# main_shema.net
KiCad netlist of a schematic drawn in EAGLE
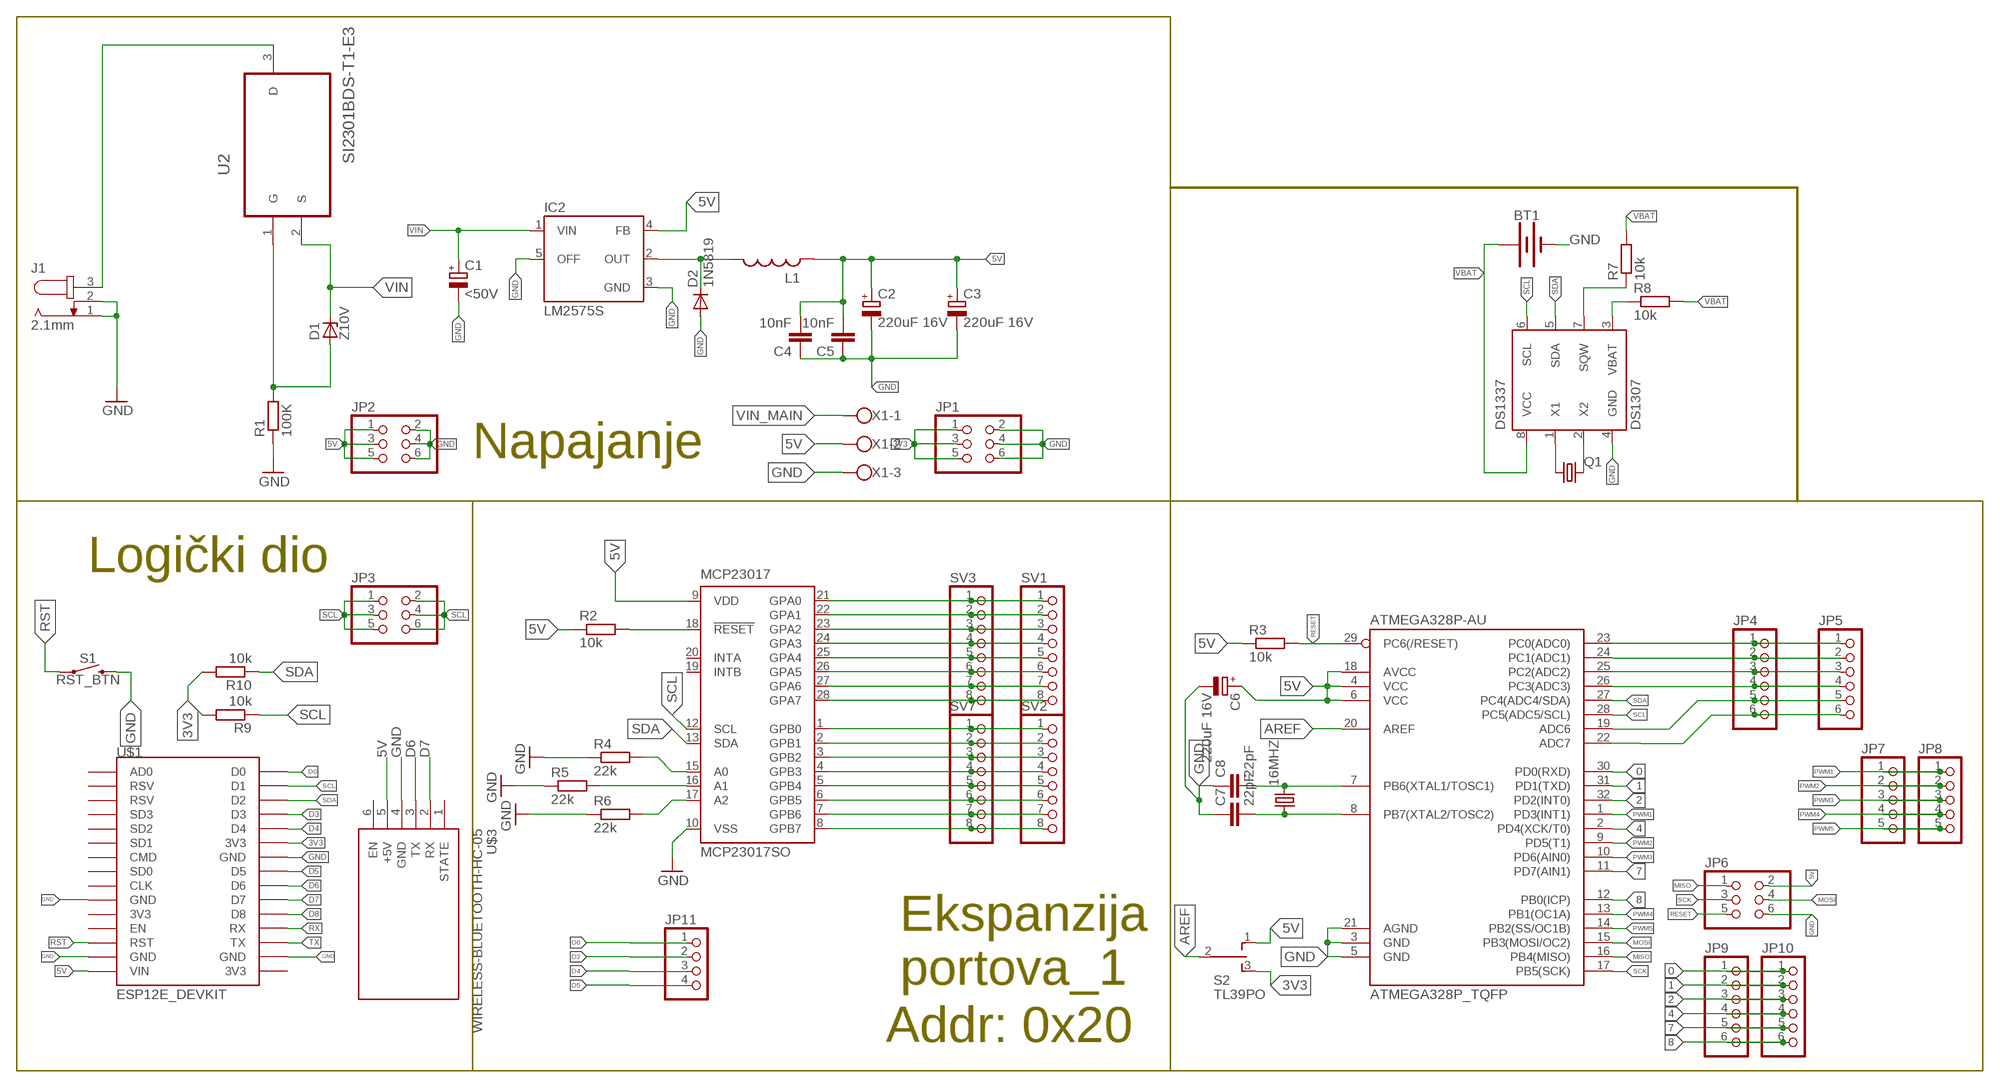
[diagram p0: schematic, sheet 1]

(export (version "E")
  (design (tool "Eeschema 10.0.6"))
  (components
    (comp (ref "16MHZ")
      (value "CRYSTALHC49S")
      (footprint "eagle-import:HC49_S")
      (libsource (lib "eagle-import") (part "crystal_204_CRYSTALHC49S"))
    )
    (comp (ref "ATMEGA328P-AU")
      (value "ATMEGA328P_TQFP")
      (footprint "eagle-import:TQFP32-08")
      (libsource (lib "eagle-import") (part "ATMEGA328P_TQFP"))
    )
    (comp (ref "BT1")
      (value "BATTERY-20MM_PTH")
      (footprint "eagle-import:BATTCOM_20MM_PTH")
      (libsource (lib "eagle-import") (part "BATTERY-20MM_PTH"))
    )
    (comp (ref "C1")
      (value "<50V")
      (footprint "eagle-import:E3,5-8")
      (libsource (lib "eagle-import") (part "CPOL-EUE3.5-8"))
    )
    (comp (ref "C2")
      (value "220uF 16V")
      (footprint "eagle-import:E2-5")
      (libsource (lib "eagle-import") (part "CPOL-EUE2-5"))
    )
    (comp (ref "C3")
      (value "220uF 16V")
      (footprint "eagle-import:E2-5")
      (libsource (lib "eagle-import") (part "CPOL-EUE2-5"))
    )
    (comp (ref "C4")
      (value "10nF")
      (footprint "eagle-import:C025-024X044")
      (libsource (lib "eagle-import") (part "C-EU025-024X044"))
    )
    (comp (ref "C5")
      (value "10nF")
      (footprint "eagle-import:C025-024X044")
      (libsource (lib "eagle-import") (part "C-EU025-024X044"))
    )
    (comp (ref "C6")
      (value "220uF 16V")
      (footprint "eagle-import:E2-5")
      (libsource (lib "eagle-import") (part "CPOL-EUE2-5"))
    )
    (comp (ref "C7")
      (value "22pF")
      (footprint "eagle-import:C025-024X044")
      (libsource (lib "eagle-import") (part "C-EU025-024X044"))
    )
    (comp (ref "C8")
      (value "22pF")
      (footprint "eagle-import:C025-024X044")
      (libsource (lib "eagle-import") (part "C-EU025-024X044"))
    )
    (comp (ref "D1")
      (value "Z10V")
      (footprint "eagle-import:DO35Z10")
      (libsource (lib "eagle-import") (part "ZENER-DIODEDO35Z10"))
    )
    (comp (ref "D2")
      (value "1N5819")
      (footprint "eagle-import:DO41-10")
      (libsource (lib "eagle-import") (part "1N4004"))
    )
    (comp (ref "DS1337")
      (value "DS1307")
      (footprint "eagle-import:DIL08")
      (libsource (lib "eagle-import") (part "DS1307"))
    )
    (comp (ref "IC2")
      (value "LM2575S")
      (footprint "eagle-import:TO263-5")
      (libsource (lib "eagle-import") (part "LM2575S"))
    )
    (comp (ref "J1")
      (value "2.1mm")
      (footprint "eagle-import:SPC4078")
      (libsource (lib "eagle-import") (part "JACK-PLUG1"))
    )
    (comp (ref "JP1")
      (value "PINHD-2X3")
      (footprint "eagle-import:2X03")
      (libsource (lib "eagle-import") (part "pinhead_2_PINHD-2X3"))
    )
    (comp (ref "JP2")
      (value "PINHD-2X3")
      (footprint "eagle-import:2X03")
      (libsource (lib "eagle-import") (part "PINHD-2X3"))
    )
    (comp (ref "JP3")
      (value "PINHD-2X3")
      (footprint "eagle-import:2X03")
      (libsource (lib "eagle-import") (part "pinhead_2_PINHD-2X3"))
    )
    (comp (ref "JP4")
      (value "PINHD-1X6")
      (footprint "eagle-import:1X06")
      (libsource (lib "eagle-import") (part "PINHD-1X6"))
    )
    (comp (ref "JP5")
      (value "PINHD-1X6")
      (footprint "eagle-import:1X06")
      (libsource (lib "eagle-import") (part "PINHD-1X6"))
    )
    (comp (ref "JP6")
      (value "PINHD-2X3")
      (footprint "eagle-import:2X03")
      (libsource (lib "eagle-import") (part "pinhead_2_PINHD-2X3"))
    )
    (comp (ref "JP7")
      (value "PINHD-1X5")
      (footprint "eagle-import:1X05")
      (libsource (lib "eagle-import") (part "PINHD-1X5"))
    )
    (comp (ref "JP8")
      (value "PINHD-1X5")
      (footprint "eagle-import:1X05")
      (libsource (lib "eagle-import") (part "PINHD-1X5"))
    )
    (comp (ref "JP9")
      (value "PINHD-1X6")
      (footprint "eagle-import:1X06")
      (libsource (lib "eagle-import") (part "PINHD-1X6"))
    )
    (comp (ref "JP10")
      (value "PINHD-1X6")
      (footprint "eagle-import:1X06")
      (libsource (lib "eagle-import") (part "PINHD-1X6"))
    )
    (comp (ref "JP11")
      (value "PINHD-1X4")
      (footprint "eagle-import:1X04")
      (libsource (lib "eagle-import") (part "PINHD-1X4"))
    )
    (comp (ref "L1")
      (value "MSS1260")
      (footprint "eagle-import:MSS1260")
      (libsource (lib "eagle-import") (part "MSS1260"))
    )
    (comp (ref "MCP23017")
      (value "MCP23017SO")
      (footprint "eagle-import:SO28W")
      (fields (field (name "MF") "MICROCHIP") (field (name "MPN") "MCP23017-E/SO"))
      (libsource (lib "eagle-import") (part "MCP23017SO"))
    )
    (comp (ref "Q1")
      (value "CRYSTALTC38H")
      (footprint "eagle-import:TC38H")
      (libsource (lib "eagle-import") (part "CRYSTALTC38H"))
    )
    (comp (ref "R1")
      (value "100K")
      (footprint "eagle-import:R1206")
      (libsource (lib "eagle-import") (part "R-EU_R1206"))
    )
    (comp (ref "R2")
      (value "10k")
      (footprint "eagle-import:R1206")
      (libsource (lib "eagle-import") (part "R-EU_R1206"))
    )
    (comp (ref "R3")
      (value "10k")
      (footprint "eagle-import:R1206")
      (libsource (lib "eagle-import") (part "R-EU_R1206"))
    )
    (comp (ref "R4")
      (value "22k")
      (footprint "eagle-import:R1206")
      (libsource (lib "eagle-import") (part "R-EU_R1206"))
    )
    (comp (ref "R5")
      (value "22k")
      (footprint "eagle-import:R1206")
      (libsource (lib "eagle-import") (part "R-EU_R1206"))
    )
    (comp (ref "R6")
      (value "22k")
      (footprint "eagle-import:R1206")
      (libsource (lib "eagle-import") (part "R-EU_R1206"))
    )
    (comp (ref "R7")
      (value "10k")
      (footprint "eagle-import:R1206")
      (libsource (lib "eagle-import") (part "R-EU_R1206"))
    )
    (comp (ref "R8")
      (value "10k")
      (footprint "eagle-import:R1206")
      (libsource (lib "eagle-import") (part "R-EU_R1206"))
    )
    (comp (ref "R9")
      (value "10k")
      (footprint "eagle-import:R1206")
      (libsource (lib "eagle-import") (part "R-EU_R1206"))
    )
    (comp (ref "R10")
      (value "10k")
      (footprint "eagle-import:R1206")
      (libsource (lib "eagle-import") (part "R-EU_R1206"))
    )
    (comp (ref "S1")
      (value "RST_BTN")
      (footprint "eagle-import:TACTILE_SWITCH_PTH_6.0MM")
      (libsource (lib "eagle-import") (part "MOMENTARY-SWITCH-SPST-PTH-6.0MM"))
    )
    (comp (ref "S2")
      (value "TL39PO")
      (footprint "eagle-import:TL3XPO")
      (libsource (lib "eagle-import") (part "TL39PO"))
    )
    (comp (ref "SV1")
      (value "PINHD-1X8")
      (footprint "eagle-import:1X08")
      (libsource (lib "eagle-import") (part "PINHD-1X8"))
    )
    (comp (ref "SV2")
      (value "PINHD-1X8")
      (footprint "eagle-import:1X08")
      (libsource (lib "eagle-import") (part "PINHD-1X8"))
    )
    (comp (ref "SV3")
      (value "PINHD-1X8")
      (footprint "eagle-import:1X08")
      (libsource (lib "eagle-import") (part "PINHD-1X8"))
    )
    (comp (ref "SV7")
      (value "PINHD-1X8")
      (footprint "eagle-import:1X08")
      (libsource (lib "eagle-import") (part "PINHD-1X8"))
    )
    (comp (ref "U$1")
      (value "ESP12E_DEVKIT")
      (footprint "eagle-import:ESP12E_DEVKIT")
      (libsource (lib "eagle-import") (part "ESP12E_DEVKIT"))
    )
    (comp (ref "U$3")
      (value "WIRELESS-BLUETOOTH-HC-05")
      (footprint "eagle-import:WIRELESS-BLUETOOTH-HC-05")
      (libsource (lib "eagle-import") (part "WIRELESS-BLUETOOTH-HC-05"))
    )
    (comp (ref "U2")
      (value "SI2301BDS-T1-E3")
      (footprint "eagle-import:SOT95P237X112-3N")
      (libsource (lib "eagle-import") (part "SI2301BDS-T1-E3"))
    )
    (comp (ref "X1")
      (value "W237-103")
      (footprint "eagle-import:W237-103")
      (fields (field (name "MPN") "237-103"))
      (libsource (lib "eagle-import") (part "W237-103"))
    )
  )
  (nets
    (net (code "1") (name "0") (class "Default")
      (node (ref "ATMEGA328P-AU") (pin "30") (pinfunction "PD0(RXD)_30") (pintype "bidirectional"))
      (node (ref "JP10") (pin "1") (pinfunction "1_1") (pintype "passive"))
      (node (ref "JP9") (pin "1") (pinfunction "1_1") (pintype "passive"))
    )
    (net (code "2") (name "1") (class "Default")
      (node (ref "ATMEGA328P-AU") (pin "31") (pinfunction "PD1(TXD)_31") (pintype "bidirectional"))
      (node (ref "JP10") (pin "2") (pinfunction "2_2") (pintype "passive"))
      (node (ref "JP9") (pin "2") (pinfunction "2_2") (pintype "passive"))
    )
    (net (code "3") (name "2") (class "Default")
      (node (ref "ATMEGA328P-AU") (pin "32") (pinfunction "PD2(INT0)_32") (pintype "bidirectional"))
      (node (ref "JP10") (pin "3") (pinfunction "3_3") (pintype "passive"))
      (node (ref "JP9") (pin "3") (pinfunction "3_3") (pintype "passive"))
    )
    (net (code "4") (name "3V3") (class "Default")
      (node (ref "JP1") (pin "1") (pinfunction "1_1") (pintype "passive"))
      (node (ref "JP1") (pin "3") (pinfunction "3_3") (pintype "passive"))
      (node (ref "JP1") (pin "5") (pinfunction "5_5") (pintype "passive"))
      (node (ref "R10") (pin "2") (pinfunction "2_2") (pintype "passive"))
      (node (ref "R9") (pin "2") (pinfunction "2_2") (pintype "passive"))
      (node (ref "S2") (pin "3") (pinfunction "S_3") (pintype "passive"))
      (node (ref "U$1") (pin "3V3@1") (pinfunction "3V3_3V3@1") (pintype "bidirectional"))
    )
    (net (code "5") (name "4") (class "Default")
      (node (ref "ATMEGA328P-AU") (pin "2") (pinfunction "PD4(XCK/T0)_2") (pintype "bidirectional"))
      (node (ref "JP10") (pin "4") (pinfunction "4_4") (pintype "passive"))
      (node (ref "JP9") (pin "4") (pinfunction "4_4") (pintype "passive"))
    )
    (net (code "6") (name "5V") (class "Default")
      (node (ref "ATMEGA328P-AU") (pin "18") (pinfunction "AVCC_18") (pintype "bidirectional"))
      (node (ref "ATMEGA328P-AU") (pin "4") (pinfunction "VCC_4") (pintype "bidirectional"))
      (node (ref "ATMEGA328P-AU") (pin "6") (pinfunction "VCC_6") (pintype "bidirectional"))
      (node (ref "C2") (pin "+") (pinfunction "+_+") (pintype "passive"))
      (node (ref "C3") (pin "+") (pinfunction "+_+") (pintype "passive"))
      (node (ref "C4") (pin "2") (pinfunction "2_2") (pintype "passive"))
      (node (ref "C5") (pin "2") (pinfunction "2_2") (pintype "passive"))
      (node (ref "C6") (pin "+") (pinfunction "+_+") (pintype "passive"))
      (node (ref "IC2") (pin "4") (pinfunction "FB_4") (pintype "input"))
      (node (ref "JP2") (pin "1") (pinfunction "1_1") (pintype "passive"))
      (node (ref "JP2") (pin "3") (pinfunction "3_3") (pintype "passive"))
      (node (ref "JP2") (pin "5") (pinfunction "5_5") (pintype "passive"))
      (node (ref "JP6") (pin "2") (pinfunction "2_2") (pintype "passive"))
      (node (ref "L1") (pin "P$2") (pinfunction "P$2_P$2") (pintype "passive"))
      (node (ref "MCP23017") (pin "9") (pinfunction "VDD_9") (pintype "power_in"))
      (node (ref "R2") (pin "1") (pinfunction "1_1") (pintype "passive"))
      (node (ref "R3") (pin "1") (pinfunction "1_1") (pintype "passive"))
      (node (ref "S2") (pin "1") (pinfunction "O_1") (pintype "passive"))
      (node (ref "U$1") (pin "VIN") (pinfunction "VIN_VIN") (pintype "bidirectional"))
      (node (ref "U$3") (pin "5") (pinfunction "+5V_5") (pintype "power_in"))
      (node (ref "X1") (pin "2") (pinfunction "KL_2") (pintype "passive"))
    )
    (net (code "7") (name "7") (class "Default")
      (node (ref "ATMEGA328P-AU") (pin "11") (pinfunction "PD7(AIN1)_11") (pintype "bidirectional"))
      (node (ref "JP10") (pin "5") (pinfunction "5_5") (pintype "passive"))
      (node (ref "JP9") (pin "5") (pinfunction "5_5") (pintype "passive"))
    )
    (net (code "8") (name "8") (class "Default")
      (node (ref "ATMEGA328P-AU") (pin "12") (pinfunction "PB0(ICP)_12") (pintype "bidirectional"))
      (node (ref "JP10") (pin "6") (pinfunction "6_6") (pintype "passive"))
      (node (ref "JP9") (pin "6") (pinfunction "6_6") (pintype "passive"))
    )
    (net (code "9") (name "AREF") (class "Default")
      (node (ref "ATMEGA328P-AU") (pin "20") (pinfunction "AREF_20") (pintype "bidirectional"))
      (node (ref "S2") (pin "2") (pinfunction "P_2") (pintype "passive"))
    )
    (net (code "10") (name "D0") (class "Default")
      (node (ref "JP11") (pin "1") (pinfunction "1_1") (pintype "passive"))
      (node (ref "U$1") (pin "D0") (pinfunction "D0_D0") (pintype "bidirectional"))
    )
    (net (code "11") (name "D3") (class "Default")
      (node (ref "JP11") (pin "2") (pinfunction "2_2") (pintype "passive"))
      (node (ref "U$1") (pin "D3") (pinfunction "D3_D3") (pintype "bidirectional"))
    )
    (net (code "12") (name "D4") (class "Default")
      (node (ref "JP11") (pin "3") (pinfunction "3_3") (pintype "passive"))
      (node (ref "U$1") (pin "D4") (pinfunction "D4_D4") (pintype "bidirectional"))
    )
    (net (code "13") (name "D5") (class "Default")
      (node (ref "JP11") (pin "4") (pinfunction "4_4") (pintype "passive"))
      (node (ref "U$1") (pin "D5") (pinfunction "D5_D5") (pintype "bidirectional"))
    )
    (net (code "14") (name "D6") (class "Default")
      (node (ref "U$1") (pin "D6") (pinfunction "D6_D6") (pintype "bidirectional"))
      (node (ref "U$3") (pin "3") (pinfunction "TX_3") (pintype "bidirectional"))
    )
    (net (code "15") (name "D7") (class "Default")
      (node (ref "U$1") (pin "D7") (pinfunction "D7_D7") (pintype "bidirectional"))
      (node (ref "U$3") (pin "2") (pinfunction "RX_2") (pintype "bidirectional"))
    )
    (net (code "16") (name "D8") (class "Default")
      (node (ref "U$1") (pin "D8") (pinfunction "D8_D8") (pintype "bidirectional"))
    )
    (net (code "17") (name "GND") (class "Default")
      (node (ref "ATMEGA328P-AU") (pin "21") (pinfunction "AGND_21") (pintype "bidirectional"))
      (node (ref "ATMEGA328P-AU") (pin "3") (pinfunction "GND_3") (pintype "bidirectional"))
      (node (ref "ATMEGA328P-AU") (pin "5") (pinfunction "GND_5") (pintype "bidirectional"))
      (node (ref "BT1") (pin "2") (pinfunction "-_2") (pintype "power_in"))
      (node (ref "C1") (pin "-") (pinfunction "-_-") (pintype "passive"))
      (node (ref "C2") (pin "-") (pinfunction "-_-") (pintype "passive"))
      (node (ref "C3") (pin "-") (pinfunction "-_-") (pintype "passive"))
      (node (ref "C4") (pin "1") (pinfunction "1_1") (pintype "passive"))
      (node (ref "C5") (pin "1") (pinfunction "1_1") (pintype "passive"))
      (node (ref "C6") (pin "-") (pinfunction "-_-") (pintype "passive"))
      (node (ref "C7") (pin "1") (pinfunction "1_1") (pintype "passive"))
      (node (ref "C8") (pin "1") (pinfunction "1_1") (pintype "passive"))
      (node (ref "D2") (pin "A") (pinfunction "A_A") (pintype "passive"))
      (node (ref "DS1337") (pin "4") (pinfunction "GND_4") (pintype "power_in"))
      (node (ref "IC2") (pin "3") (pinfunction "GND_3") (pintype "power_in"))
      (node (ref "IC2") (pin "5") (pinfunction "OFF_5") (pintype "input"))
      (node (ref "J1") (pin "1") (pinfunction "1_1") (pintype "passive"))
      (node (ref "J1") (pin "2") (pinfunction "2_2") (pintype "passive"))
      (node (ref "JP1") (pin "2") (pinfunction "2_2") (pintype "passive"))
      (node (ref "JP1") (pin "4") (pinfunction "4_4") (pintype "passive"))
      (node (ref "JP1") (pin "6") (pinfunction "6_6") (pintype "passive"))
      (node (ref "JP2") (pin "2") (pinfunction "2_2") (pintype "passive"))
      (node (ref "JP2") (pin "4") (pinfunction "4_4") (pintype "passive"))
      (node (ref "JP2") (pin "6") (pinfunction "6_6") (pintype "passive"))
      (node (ref "JP6") (pin "6") (pinfunction "6_6") (pintype "passive"))
      (node (ref "MCP23017") (pin "10") (pinfunction "VSS_10") (pintype "power_in"))
      (node (ref "R1") (pin "1") (pinfunction "1_1") (pintype "passive"))
      (node (ref "R4") (pin "1") (pinfunction "1_1") (pintype "passive"))
      (node (ref "R5") (pin "1") (pinfunction "1_1") (pintype "passive"))
      (node (ref "R6") (pin "1") (pinfunction "1_1") (pintype "passive"))
      (node (ref "S1") (pin "3") (pinfunction "2_3") (pintype "passive"))
      (node (ref "U$1") (pin "GND@0") (pinfunction "GND_GND@0") (pintype "bidirectional"))
      (node (ref "U$1") (pin "GND@1") (pinfunction "GND_GND@1") (pintype "bidirectional"))
      (node (ref "U$1") (pin "GND@2") (pinfunction "GND_GND@2") (pintype "bidirectional"))
      (node (ref "U$1") (pin "GND@3") (pinfunction "GND_GND@3") (pintype "bidirectional"))
      (node (ref "U$3") (pin "4") (pinfunction "GND_4") (pintype "power_in"))
      (node (ref "X1") (pin "3") (pinfunction "KL_3") (pintype "passive"))
    )
    (net (code "18") (name "MISO") (class "Default")
      (node (ref "ATMEGA328P-AU") (pin "16") (pinfunction "PB4(MISO)_16") (pintype "bidirectional"))
      (node (ref "JP6") (pin "1") (pinfunction "1_1") (pintype "passive"))
    )
    (net (code "19") (name "MOSI") (class "Default")
      (node (ref "ATMEGA328P-AU") (pin "15") (pinfunction "PB3(MOSI/OC2)_15") (pintype "bidirectional"))
      (node (ref "JP6") (pin "4") (pinfunction "4_4") (pintype "passive"))
    )
    (net (code "20") (name "Net-(ATMEGA328P-AU-ADC6)") (class "Default")
      (node (ref "ATMEGA328P-AU") (pin "19") (pinfunction "ADC6_19") (pintype "bidirectional"))
      (node (ref "JP4") (pin "5") (pinfunction "5_5") (pintype "passive"))
      (node (ref "JP5") (pin "5") (pinfunction "5_5") (pintype "passive"))
    )
    (net (code "21") (name "Net-(ATMEGA328P-AU-ADC7)") (class "Default")
      (node (ref "ATMEGA328P-AU") (pin "22") (pinfunction "ADC7_22") (pintype "bidirectional"))
      (node (ref "JP4") (pin "6") (pinfunction "6_6") (pintype "passive"))
      (node (ref "JP5") (pin "6") (pinfunction "6_6") (pintype "passive"))
    )
    (net (code "22") (name "Net-(ATMEGA328P-AU-PB6(XTAL1{slash}TOSC1))") (class "Default")
      (node (ref "16MHZ") (pin "2") (pinfunction "2_2") (pintype "passive"))
      (node (ref "ATMEGA328P-AU") (pin "7") (pinfunction "PB6(XTAL1/TOSC1)_7") (pintype "bidirectional"))
      (node (ref "C8") (pin "2") (pinfunction "2_2") (pintype "passive"))
    )
    (net (code "23") (name "Net-(ATMEGA328P-AU-PB7(XTAL2{slash}TOSC2))") (class "Default")
      (node (ref "16MHZ") (pin "1") (pinfunction "1_1") (pintype "passive"))
      (node (ref "ATMEGA328P-AU") (pin "8") (pinfunction "PB7(XTAL2/TOSC2)_8") (pintype "bidirectional"))
      (node (ref "C7") (pin "2") (pinfunction "2_2") (pintype "passive"))
    )
    (net (code "24") (name "Net-(ATMEGA328P-AU-PC0(ADC0))") (class "Default")
      (node (ref "ATMEGA328P-AU") (pin "23") (pinfunction "PC0(ADC0)_23") (pintype "bidirectional"))
      (node (ref "JP4") (pin "1") (pinfunction "1_1") (pintype "passive"))
      (node (ref "JP5") (pin "1") (pinfunction "1_1") (pintype "passive"))
    )
    (net (code "25") (name "Net-(ATMEGA328P-AU-PC1(ADC1))") (class "Default")
      (node (ref "ATMEGA328P-AU") (pin "24") (pinfunction "PC1(ADC1)_24") (pintype "bidirectional"))
      (node (ref "JP4") (pin "2") (pinfunction "2_2") (pintype "passive"))
      (node (ref "JP5") (pin "2") (pinfunction "2_2") (pintype "passive"))
    )
    (net (code "26") (name "Net-(ATMEGA328P-AU-PC2(ADC2))") (class "Default")
      (node (ref "ATMEGA328P-AU") (pin "25") (pinfunction "PC2(ADC2)_25") (pintype "bidirectional"))
      (node (ref "JP4") (pin "3") (pinfunction "3_3") (pintype "passive"))
      (node (ref "JP5") (pin "3") (pinfunction "3_3") (pintype "passive"))
    )
    (net (code "27") (name "Net-(ATMEGA328P-AU-PC3(ADC3))") (class "Default")
      (node (ref "ATMEGA328P-AU") (pin "26") (pinfunction "PC3(ADC3)_26") (pintype "bidirectional"))
      (node (ref "JP4") (pin "4") (pinfunction "4_4") (pintype "passive"))
      (node (ref "JP5") (pin "4") (pinfunction "4_4") (pintype "passive"))
    )
    (net (code "28") (name "Net-(DS1337-SQW)") (class "Default")
      (node (ref "DS1337") (pin "7") (pinfunction "SQW_7") (pintype "open_collector"))
      (node (ref "R7") (pin "1") (pinfunction "1_1") (pintype "passive"))
    )
    (net (code "29") (name "Net-(DS1337-VBAT)") (class "Default")
      (node (ref "DS1337") (pin "3") (pinfunction "VBAT_3") (pintype "passive"))
      (node (ref "R8") (pin "1") (pinfunction "1_1") (pintype "passive"))
    )
    (net (code "30") (name "Net-(DS1337-X1)") (class "Default")
      (node (ref "DS1337") (pin "1") (pinfunction "X1_1") (pintype "input"))
      (node (ref "Q1") (pin "1") (pinfunction "1_1") (pintype "passive"))
    )
    (net (code "31") (name "Net-(DS1337-X2)") (class "Default")
      (node (ref "DS1337") (pin "2") (pinfunction "X2_2") (pintype "output"))
      (node (ref "Q1") (pin "2") (pinfunction "2_2") (pintype "passive"))
    )
    (net (code "32") (name "Net-(IC2-OUT)") (class "Default")
      (node (ref "D2") (pin "C") (pinfunction "C_C") (pintype "passive"))
      (node (ref "IC2") (pin "2") (pinfunction "OUT_2") (pintype "output"))
      (node (ref "L1") (pin "P$1") (pinfunction "P$1_P$1") (pintype "passive"))
    )
    (net (code "33") (name "Net-(MCP23017-A0)") (class "Default")
      (node (ref "MCP23017") (pin "15") (pinfunction "A0_15") (pintype "input"))
      (node (ref "R4") (pin "2") (pinfunction "2_2") (pintype "passive"))
    )
    (net (code "34") (name "Net-(MCP23017-A1)") (class "Default")
      (node (ref "MCP23017") (pin "16") (pinfunction "A1_16") (pintype "input"))
      (node (ref "R5") (pin "2") (pinfunction "2_2") (pintype "passive"))
    )
    (net (code "35") (name "Net-(MCP23017-A2)") (class "Default")
      (node (ref "MCP23017") (pin "17") (pinfunction "A2_17") (pintype "input"))
      (node (ref "R6") (pin "2") (pinfunction "2_2") (pintype "passive"))
    )
    (net (code "36") (name "Net-(MCP23017-GPA0)") (class "Default")
      (node (ref "MCP23017") (pin "21") (pinfunction "GPA0_21") (pintype "bidirectional"))
      (node (ref "SV1") (pin "1") (pinfunction "1_1") (pintype "passive"))
      (node (ref "SV3") (pin "1") (pinfunction "1_1") (pintype "passive"))
    )
    (net (code "37") (name "Net-(MCP23017-GPA1)") (class "Default")
      (node (ref "MCP23017") (pin "22") (pinfunction "GPA1_22") (pintype "bidirectional"))
      (node (ref "SV1") (pin "2") (pinfunction "2_2") (pintype "passive"))
      (node (ref "SV3") (pin "2") (pinfunction "2_2") (pintype "passive"))
    )
    (net (code "38") (name "Net-(MCP23017-GPA2)") (class "Default")
      (node (ref "MCP23017") (pin "23") (pinfunction "GPA2_23") (pintype "bidirectional"))
      (node (ref "SV1") (pin "3") (pinfunction "3_3") (pintype "passive"))
      (node (ref "SV3") (pin "3") (pinfunction "3_3") (pintype "passive"))
    )
    (net (code "39") (name "Net-(MCP23017-GPA3)") (class "Default")
      (node (ref "MCP23017") (pin "24") (pinfunction "GPA3_24") (pintype "bidirectional"))
      (node (ref "SV1") (pin "4") (pinfunction "4_4") (pintype "passive"))
      (node (ref "SV3") (pin "4") (pinfunction "4_4") (pintype "passive"))
    )
    (net (code "40") (name "Net-(MCP23017-GPA4)") (class "Default")
      (node (ref "MCP23017") (pin "25") (pinfunction "GPA4_25") (pintype "bidirectional"))
      (node (ref "SV1") (pin "5") (pinfunction "5_5") (pintype "passive"))
      (node (ref "SV3") (pin "5") (pinfunction "5_5") (pintype "passive"))
    )
    (net (code "41") (name "Net-(MCP23017-GPA5)") (class "Default")
      (node (ref "MCP23017") (pin "26") (pinfunction "GPA5_26") (pintype "bidirectional"))
      (node (ref "SV1") (pin "6") (pinfunction "6_6") (pintype "passive"))
      (node (ref "SV3") (pin "6") (pinfunction "6_6") (pintype "passive"))
    )
    (net (code "42") (name "Net-(MCP23017-GPA6)") (class "Default")
      (node (ref "MCP23017") (pin "27") (pinfunction "GPA6_27") (pintype "bidirectional"))
      (node (ref "SV1") (pin "7") (pinfunction "7_7") (pintype "passive"))
      (node (ref "SV3") (pin "7") (pinfunction "7_7") (pintype "passive"))
    )
    (net (code "43") (name "Net-(MCP23017-GPA7)") (class "Default")
      (node (ref "MCP23017") (pin "28") (pinfunction "GPA7_28") (pintype "bidirectional"))
      (node (ref "SV1") (pin "8") (pinfunction "8_8") (pintype "passive"))
      (node (ref "SV3") (pin "8") (pinfunction "8_8") (pintype "passive"))
    )
    (net (code "44") (name "Net-(MCP23017-GPB0)") (class "Default")
      (node (ref "MCP23017") (pin "1") (pinfunction "GPB0_1") (pintype "bidirectional"))
      (node (ref "SV2") (pin "1") (pinfunction "1_1") (pintype "passive"))
      (node (ref "SV7") (pin "1") (pinfunction "1_1") (pintype "passive"))
    )
    (net (code "45") (name "Net-(MCP23017-GPB1)") (class "Default")
      (node (ref "MCP23017") (pin "2") (pinfunction "GPB1_2") (pintype "bidirectional"))
      (node (ref "SV2") (pin "2") (pinfunction "2_2") (pintype "passive"))
      (node (ref "SV7") (pin "2") (pinfunction "2_2") (pintype "passive"))
    )
    (net (code "46") (name "Net-(MCP23017-GPB2)") (class "Default")
      (node (ref "MCP23017") (pin "3") (pinfunction "GPB2_3") (pintype "bidirectional"))
      (node (ref "SV2") (pin "3") (pinfunction "3_3") (pintype "passive"))
      (node (ref "SV7") (pin "3") (pinfunction "3_3") (pintype "passive"))
    )
    (net (code "47") (name "Net-(MCP23017-GPB3)") (class "Default")
      (node (ref "MCP23017") (pin "4") (pinfunction "GPB3_4") (pintype "bidirectional"))
      (node (ref "SV2") (pin "4") (pinfunction "4_4") (pintype "passive"))
      (node (ref "SV7") (pin "4") (pinfunction "4_4") (pintype "passive"))
    )
    (net (code "48") (name "Net-(MCP23017-GPB4)") (class "Default")
      (node (ref "MCP23017") (pin "5") (pinfunction "GPB4_5") (pintype "bidirectional"))
      (node (ref "SV2") (pin "5") (pinfunction "5_5") (pintype "passive"))
      (node (ref "SV7") (pin "5") (pinfunction "5_5") (pintype "passive"))
    )
    (net (code "49") (name "Net-(MCP23017-GPB5)") (class "Default")
      (node (ref "MCP23017") (pin "6") (pinfunction "GPB5_6") (pintype "bidirectional"))
      (node (ref "SV2") (pin "6") (pinfunction "6_6") (pintype "passive"))
      (node (ref "SV7") (pin "6") (pinfunction "6_6") (pintype "passive"))
    )
    (net (code "50") (name "Net-(MCP23017-GPB6)") (class "Default")
      (node (ref "MCP23017") (pin "7") (pinfunction "GPB6_7") (pintype "bidirectional"))
      (node (ref "SV2") (pin "7") (pinfunction "7_7") (pintype "passive"))
      (node (ref "SV7") (pin "7") (pinfunction "7_7") (pintype "passive"))
    )
    (net (code "51") (name "Net-(MCP23017-GPB7)") (class "Default")
      (node (ref "MCP23017") (pin "8") (pinfunction "GPB7_8") (pintype "bidirectional"))
      (node (ref "SV2") (pin "8") (pinfunction "8_8") (pintype "passive"))
      (node (ref "SV7") (pin "8") (pinfunction "8_8") (pintype "passive"))
    )
    (net (code "52") (name "Net-(MCP23017-~{RESET})") (class "Default")
      (node (ref "MCP23017") (pin "18") (pinfunction "~{RESET}_18") (pintype "input"))
      (node (ref "R2") (pin "2") (pinfunction "2_2") (pintype "passive"))
    )
    (net (code "53") (name "Net-(U2-G)") (class "Default")
      (node (ref "D1") (pin "A") (pinfunction "A_A") (pintype "passive"))
      (node (ref "R1") (pin "2") (pinfunction "2_2") (pintype "passive"))
      (node (ref "U2") (pin "1") (pinfunction "G_1") (pintype "passive"))
    )
    (net (code "54") (name "PWM1") (class "Default")
      (node (ref "ATMEGA328P-AU") (pin "1") (pinfunction "PD3(INT1)_1") (pintype "bidirectional"))
      (node (ref "JP7") (pin "1") (pinfunction "1_1") (pintype "passive"))
      (node (ref "JP8") (pin "1") (pinfunction "1_1") (pintype "passive"))
    )
    (net (code "55") (name "PWM2") (class "Default")
      (node (ref "ATMEGA328P-AU") (pin "9") (pinfunction "PD5(T1)_9") (pintype "bidirectional"))
      (node (ref "JP7") (pin "2") (pinfunction "2_2") (pintype "passive"))
      (node (ref "JP8") (pin "2") (pinfunction "2_2") (pintype "passive"))
    )
    (net (code "56") (name "PWM3") (class "Default")
      (node (ref "ATMEGA328P-AU") (pin "10") (pinfunction "PD6(AIN0)_10") (pintype "bidirectional"))
      (node (ref "JP7") (pin "3") (pinfunction "3_3") (pintype "passive"))
      (node (ref "JP8") (pin "3") (pinfunction "3_3") (pintype "passive"))
    )
    (net (code "57") (name "PWM4") (class "Default")
      (node (ref "ATMEGA328P-AU") (pin "13") (pinfunction "PB1(OC1A)_13") (pintype "bidirectional"))
      (node (ref "JP7") (pin "4") (pinfunction "4_4") (pintype "passive"))
      (node (ref "JP8") (pin "4") (pinfunction "4_4") (pintype "passive"))
    )
    (net (code "58") (name "PWM5") (class "Default")
      (node (ref "ATMEGA328P-AU") (pin "14") (pinfunction "PB2(SS/OC1B)_14") (pintype "bidirectional"))
      (node (ref "JP7") (pin "5") (pinfunction "5_5") (pintype "passive"))
      (node (ref "JP8") (pin "5") (pinfunction "5_5") (pintype "passive"))
    )
    (net (code "59") (name "RESET") (class "Default")
      (node (ref "ATMEGA328P-AU") (pin "29") (pinfunction "PC6(/RESET)_29") (pintype "bidirectional"))
      (node (ref "JP6") (pin "5") (pinfunction "5_5") (pintype "passive"))
      (node (ref "R3") (pin "2") (pinfunction "2_2") (pintype "passive"))
    )
    (net (code "60") (name "RST") (class "Default")
      (node (ref "S1") (pin "1") (pinfunction "1_1") (pintype "passive"))
      (node (ref "U$1") (pin "RST") (pinfunction "RST_RST") (pintype "bidirectional"))
    )
    (net (code "61") (name "RX") (class "Default")
      (node (ref "U$1") (pin "RX") (pinfunction "RX_RX") (pintype "bidirectional"))
    )
    (net (code "62") (name "SCK") (class "Default")
      (node (ref "ATMEGA328P-AU") (pin "17") (pinfunction "PB5(SCK)_17") (pintype "bidirectional"))
      (node (ref "JP6") (pin "3") (pinfunction "3_3") (pintype "passive"))
    )
    (net (code "63") (name "SCL") (class "Default")
      (node (ref "ATMEGA328P-AU") (pin "28") (pinfunction "PC5(ADC5/SCL)_28") (pintype "bidirectional"))
      (node (ref "DS1337") (pin "6") (pinfunction "SCL_6") (pintype "input"))
      (node (ref "JP3") (pin "1") (pinfunction "1_1") (pintype "passive"))
      (node (ref "JP3") (pin "3") (pinfunction "3_3") (pintype "passive"))
      (node (ref "JP3") (pin "5") (pinfunction "5_5") (pintype "passive"))
      (node (ref "MCP23017") (pin "12") (pinfunction "SCL_12") (pintype "input"))
      (node (ref "R9") (pin "1") (pinfunction "1_1") (pintype "passive"))
      (node (ref "U$1") (pin "D1") (pinfunction "D1_D1") (pintype "bidirectional"))
    )
    (net (code "64") (name "SDA") (class "Default")
      (node (ref "ATMEGA328P-AU") (pin "27") (pinfunction "PC4(ADC4/SDA)_27") (pintype "bidirectional"))
      (node (ref "DS1337") (pin "5") (pinfunction "SDA_5") (pintype "bidirectional"))
      (node (ref "JP3") (pin "2") (pinfunction "2_2") (pintype "passive"))
      (node (ref "JP3") (pin "4") (pinfunction "4_4") (pintype "passive"))
      (node (ref "JP3") (pin "6") (pinfunction "6_6") (pintype "passive"))
      (node (ref "MCP23017") (pin "13") (pinfunction "SDA_13") (pintype "bidirectional"))
      (node (ref "R10") (pin "1") (pinfunction "1_1") (pintype "passive"))
      (node (ref "U$1") (pin "D2") (pinfunction "D2_D2") (pintype "bidirectional"))
    )
    (net (code "65") (name "TX") (class "Default")
      (node (ref "U$1") (pin "TX") (pinfunction "TX_TX") (pintype "bidirectional"))
    )
    (net (code "66") (name "VBAT") (class "Default")
      (node (ref "BT1") (pin "1") (pinfunction "+_1") (pintype "power_in"))
      (node (ref "DS1337") (pin "8") (pinfunction "VCC_8") (pintype "power_in"))
      (node (ref "R7") (pin "2") (pinfunction "2_2") (pintype "passive"))
      (node (ref "R8") (pin "2") (pinfunction "2_2") (pintype "passive"))
    )
    (net (code "67") (name "VIN") (class "Default")
      (node (ref "C1") (pin "+") (pinfunction "+_+") (pintype "passive"))
      (node (ref "D1") (pin "C") (pinfunction "C_C") (pintype "passive"))
      (node (ref "IC2") (pin "1") (pinfunction "VIN_1") (pintype "power_in"))
      (node (ref "U2") (pin "2") (pinfunction "S_2") (pintype "passive"))
    )
    (net (code "68") (name "VIN_MAIN") (class "Default")
      (node (ref "J1") (pin "3") (pinfunction "3_3") (pintype "passive"))
      (node (ref "U2") (pin "3") (pinfunction "D_3") (pintype "passive"))
      (node (ref "X1") (pin "1") (pinfunction "KL_1") (pintype "passive"))
    )
    (net (code "69") (name "unconnected-(MCP23017-INTA-Pad20)") (class "Default")
      (node (ref "MCP23017") (pin "20") (pinfunction "INTA_20") (pintype "output"))
    )
    (net (code "70") (name "unconnected-(MCP23017-INTB-Pad19)") (class "Default")
      (node (ref "MCP23017") (pin "19") (pinfunction "INTB_19") (pintype "output"))
    )
    (net (code "71") (name "unconnected-(U$1-3V3-Pad3V3@0)") (class "Default")
      (node (ref "U$1") (pin "3V3@0") (pinfunction "3V3_3V3@0") (pintype "bidirectional"))
    )
    (net (code "72") (name "unconnected-(U$1-3V3-Pad3V3@2)") (class "Default")
      (node (ref "U$1") (pin "3V3@2") (pinfunction "3V3_3V3@2") (pintype "bidirectional"))
    )
    (net (code "73") (name "unconnected-(U$1-PadAD0)") (class "Default")
      (node (ref "U$1") (pin "AD0") (pinfunction "AD0_AD0") (pintype "bidirectional"))
    )
    (net (code "74") (name "unconnected-(U$1-PadCLK)") (class "Default")
      (node (ref "U$1") (pin "CLK") (pinfunction "CLK_CLK") (pintype "bidirectional"))
    )
    (net (code "75") (name "unconnected-(U$1-PadCMD)") (class "Default")
      (node (ref "U$1") (pin "CMD") (pinfunction "CMD_CMD") (pintype "bidirectional"))
    )
    (net (code "76") (name "unconnected-(U$1-PadEN)") (class "Default")
      (node (ref "U$1") (pin "EN") (pinfunction "EN_EN") (pintype "bidirectional"))
    )
    (net (code "77") (name "unconnected-(U$1-PadSD0)") (class "Default")
      (node (ref "U$1") (pin "SD0") (pinfunction "SD0_SD0") (pintype "bidirectional"))
    )
    (net (code "78") (name "unconnected-(U$1-PadSD1)") (class "Default")
      (node (ref "U$1") (pin "SD1") (pinfunction "SD1_SD1") (pintype "bidirectional"))
    )
    (net (code "79") (name "unconnected-(U$1-PadSD2)") (class "Default")
      (node (ref "U$1") (pin "SD2") (pinfunction "SD2_SD2") (pintype "bidirectional"))
    )
    (net (code "80") (name "unconnected-(U$1-PadSD3)") (class "Default")
      (node (ref "U$1") (pin "SD3") (pinfunction "SD3_SD3") (pintype "bidirectional"))
    )
    (net (code "81") (name "unconnected-(U$1-RSV-PadRSV@0)") (class "Default")
      (node (ref "U$1") (pin "RSV@0") (pinfunction "RSV_RSV@0") (pintype "bidirectional"))
    )
    (net (code "82") (name "unconnected-(U$1-RSV-PadRSV@1)") (class "Default")
      (node (ref "U$1") (pin "RSV@1") (pinfunction "RSV_RSV@1") (pintype "bidirectional"))
    )
    (net (code "83") (name "unconnected-(U$3-EN-Pad6)") (class "Default")
      (node (ref "U$3") (pin "6") (pinfunction "EN_6") (pintype "bidirectional"))
    )
    (net (code "84") (name "unconnected-(U$3-STATE-Pad1)") (class "Default")
      (node (ref "U$3") (pin "1") (pinfunction "STATE_1") (pintype "bidirectional"))
    )
  )
)
